# Sheet1.net
KiCad netlist of a schematic drawn in Altium Designer
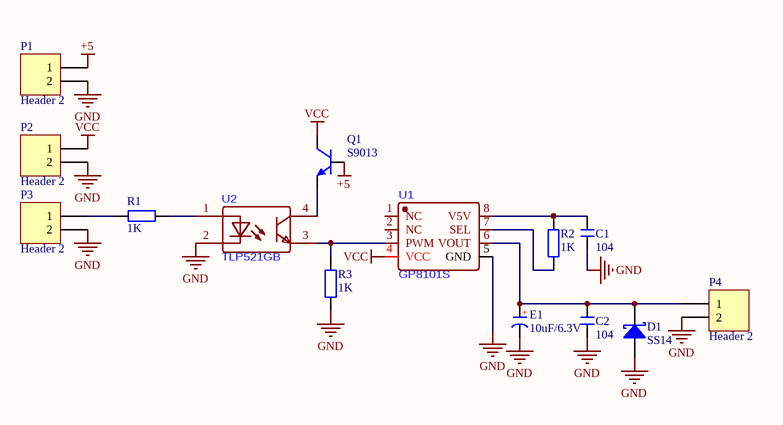
[diagram p0: Sheet1.SchDoc]

(export (version "E")
  (design (tool "Eeschema 10.0.6"))
  (components
    (comp (ref "C1")
      (value "104")
      (footprint "C 0805_L")
      (description "贴片电容")
      (libsource (lib "01 - 电容-电阻-电感") (part "C"))
    )
    (comp (ref "C2")
      (value "104")
      (footprint "C 0805_L")
      (description "贴片电容")
      (libsource (lib "01 - 电容-电阻-电感") (part "C"))
    )
    (comp (ref "D1")
      (value "SS14")
      (footprint "SMA")
      (description "肖特基二极管")
      (libsource (lib "02 - 二极管(LED)-三极管-整流桥") (part "SS14"))
    )
    (comp (ref "E1")
      (value "10uF/6.3V")
      (footprint "CS 2.0*5*8 - C")
      (description "直插固态电容")
      (libsource (lib "01 - 电容-电阻-电感") (part "CS"))
    )
    (comp (ref "P1")
      (value "Header 2")
      (footprint "HDR1X2")
      (description "Header, 2-Pin")
      (fields (field (name "PUBLISHER") "Altium Limited"))
      (libsource (lib "") (part "Header 2_1"))
    )
    (comp (ref "P2")
      (value "Header 2")
      (footprint "HDR1X2")
      (description "Header, 2-Pin")
      (fields (field (name "PUBLISHER") "Altium Limited"))
      (libsource (lib "") (part "Header 2_1"))
    )
    (comp (ref "P3")
      (value "Header 2")
      (footprint "HDR1X2")
      (description "Header, 2-Pin")
      (fields (field (name "PUBLISHER") "Altium Limited"))
      (libsource (lib "") (part "Header 2_1"))
    )
    (comp (ref "P4")
      (value "Header 2")
      (footprint "HDR1X2")
      (description "Header, 2-Pin")
      (fields (field (name "PUBLISHER") "Altium Limited"))
      (libsource (lib "Miscellaneous Connectors") (part "Header 2"))
    )
    (comp (ref "Q1")
      (value "S9013")
      (footprint "TO92A")
      (description "低频放大-NPN型")
      (libsource (lib "02 - 二极管(LED)-三极管-整流桥") (part "9013-DIP"))
    )
    (comp (ref "R1")
      (value "1K")
      (footprint "R 0805_L")
      (description "贴片电阻")
      (libsource (lib "01 - 电容-电阻-电感") (part "R"))
    )
    (comp (ref "R2")
      (value "1K")
      (footprint "R 0805_L")
      (description "贴片电阻")
      (libsource (lib "01 - 电容-电阻-电感") (part "R"))
    )
    (comp (ref "R3")
      (value "1K")
      (footprint "R 0805_L")
      (description "贴片电阻")
      (libsource (lib "01 - 电容-电阻-电感") (part "R"))
    )
    (comp (ref "U1")
      (value "GP8101S")
      (footprint "SOIC-8_L4.9-W3.9-P1.27-LS6.0-TR")
      (libsource (lib "GP8101S_2022-06-30") (part "GP8101S"))
    )
    (comp (ref "U2")
      (value "TLP521GB")
      (footprint "DIP-4_L6.4-W4.6-P2.54-LS7.6-BL")
      (libsource (lib "TLP521GB_2022-06-30") (part "TLP521GB"))
    )
  )
  (nets
    (net (code "1") (name "+5") (class "Default")
      (node (ref "P1") (pin "1") (pinfunction "1_1") (pintype "passive"))
      (node (ref "Q1") (pin "2") (pinfunction "B_2") (pintype "passive"))
    )
    (net (code "2") (name "GND") (class "Default")
      (node (ref "C1") (pin "1") (pinfunction "1_1") (pintype "passive"))
      (node (ref "C2") (pin "1") (pinfunction "1_1") (pintype "passive"))
      (node (ref "D1") (pin "1") (pinfunction "A_1") (pintype "passive"))
      (node (ref "E1") (pin "2") (pinfunction "K_2") (pintype "passive"))
      (node (ref "P1") (pin "2") (pinfunction "2_2") (pintype "passive"))
      (node (ref "P2") (pin "2") (pinfunction "2_2") (pintype "passive"))
      (node (ref "P3") (pin "2") (pinfunction "2_2") (pintype "passive"))
      (node (ref "P4") (pin "2") (pinfunction "2_2") (pintype "passive"))
      (node (ref "R3") (pin "1") (pinfunction "1_1") (pintype "passive"))
      (node (ref "U1") (pin "5") (pinfunction "GND_5") (pintype "passive"))
      (node (ref "U2") (pin "2") (pinfunction "2_2") (pintype "passive"))
    )
    (net (code "3") (name "Net-(D1-K)") (class "Default")
      (node (ref "C2") (pin "2") (pinfunction "2_2") (pintype "passive"))
      (node (ref "D1") (pin "2") (pinfunction "K_2") (pintype "passive"))
      (node (ref "E1") (pin "1") (pinfunction "A_1") (pintype "passive"))
      (node (ref "P4") (pin "1") (pinfunction "1_1") (pintype "passive"))
      (node (ref "U1") (pin "6") (pinfunction "VOUT_6") (pintype "passive"))
    )
    (net (code "4") (name "Net-(P3-Pad1)") (class "Default")
      (node (ref "P3") (pin "1") (pinfunction "1_1") (pintype "passive"))
      (node (ref "R1") (pin "1") (pinfunction "1_1") (pintype "passive"))
    )
    (net (code "5") (name "Net-(Q1-E)") (class "Default")
      (node (ref "Q1") (pin "1") (pinfunction "E_1") (pintype "passive"))
      (node (ref "U2") (pin "4") (pinfunction "4_4") (pintype "passive"))
    )
    (net (code "6") (name "Net-(R1-Pad2)") (class "Default")
      (node (ref "R1") (pin "2") (pinfunction "2_2") (pintype "passive"))
      (node (ref "U2") (pin "1") (pinfunction "1_1") (pintype "passive"))
    )
    (net (code "7") (name "Net-(U1-PWM)") (class "Default")
      (node (ref "R3") (pin "2") (pinfunction "2_2") (pintype "passive"))
      (node (ref "U1") (pin "3") (pinfunction "PWM_3") (pintype "passive"))
      (node (ref "U2") (pin "3") (pinfunction "3_3") (pintype "passive"))
    )
    (net (code "8") (name "Net-(U1-SEL)") (class "Default")
      (node (ref "R2") (pin "1") (pinfunction "1_1") (pintype "passive"))
      (node (ref "U1") (pin "7") (pinfunction "SEL_7") (pintype "passive"))
    )
    (net (code "9") (name "Net-(U1-V5V)") (class "Default")
      (node (ref "C1") (pin "2") (pinfunction "2_2") (pintype "passive"))
      (node (ref "R2") (pin "2") (pinfunction "2_2") (pintype "passive"))
      (node (ref "U1") (pin "8") (pinfunction "V5V_8") (pintype "passive"))
    )
    (net (code "10") (name "VCC") (class "Default")
      (node (ref "P2") (pin "1") (pinfunction "1_1") (pintype "passive"))
      (node (ref "Q1") (pin "3") (pinfunction "C_3") (pintype "passive"))
      (node (ref "U1") (pin "4") (pinfunction "VCC_4") (pintype "passive"))
    )
    (net (code "11") (name "unconnected-(U1-NC-Pad1)") (class "Default")
      (node (ref "U1") (pin "1") (pinfunction "NC_1") (pintype "passive"))
    )
    (net (code "12") (name "unconnected-(U1-NC-Pad2)") (class "Default")
      (node (ref "U1") (pin "2") (pinfunction "NC_2") (pintype "passive"))
    )
  )
)
